# DC_Motor_Direction_Control.net
KiCad netlist of a schematic drawn in EAGLE
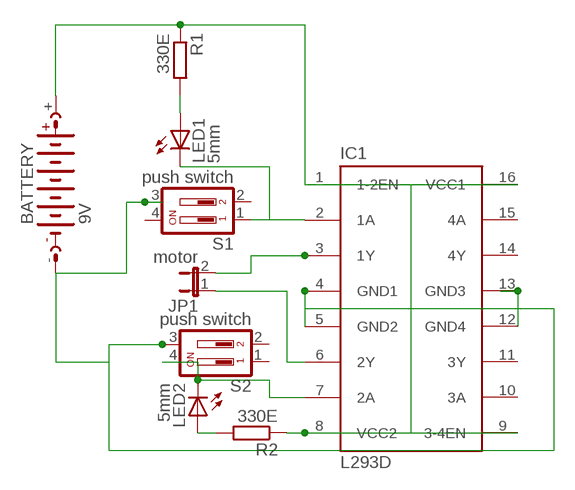
[diagram p0: schematic, sheet 1]

(export (version "E")
  (design (tool "Eeschema 10.0.6"))
  (components
    (comp (ref "BATTERY")
      (value "9V")
      (footprint "eagle-import:AB9V")
      (libsource (lib "eagle-import") (part "AB9V"))
    )
    (comp (ref "IC1")
      (value "L293D")
      (footprint "eagle-import:DIL16")
      (libsource (lib "eagle-import") (part "L293D"))
    )
    (comp (ref "JP1")
      (value "motor")
      (footprint "eagle-import:JP1")
      (libsource (lib "eagle-import") (part "JP1E"))
    )
    (comp (ref "LED1")
      (value "5mm")
      (footprint "eagle-import:LED5MM")
      (libsource (lib "eagle-import") (part "LED5MM"))
    )
    (comp (ref "LED2")
      (value "5mm")
      (footprint "eagle-import:LED5MM")
      (libsource (lib "eagle-import") (part "LED5MM"))
    )
    (comp (ref "R1")
      (value "330E")
      (footprint "eagle-import:0204_7")
      (libsource (lib "eagle-import") (part "R-EU_0204/7"))
    )
    (comp (ref "R2")
      (value "330E")
      (footprint "eagle-import:0204_7")
      (libsource (lib "eagle-import") (part "R-EU_0204/7"))
    )
    (comp (ref "S1")
      (value "push switch")
      (footprint "eagle-import:DS-02")
      (libsource (lib "eagle-import") (part "DS02"))
    )
    (comp (ref "S2")
      (value "push switch")
      (footprint "eagle-import:DS-02")
      (libsource (lib "eagle-import") (part "DS02"))
    )
  )
  (nets
    (net (code "1") (name "Net-(IC1-1-2EN)") (class "Default")
      (node (ref "BATTERY") (pin "+") (pinfunction "+_+") (pintype "passive"))
      (node (ref "IC1") (pin "1") (pinfunction "1-2EN_1") (pintype "input"))
      (node (ref "IC1") (pin "16") (pinfunction "VCC1_16") (pintype "power_in"))
      (node (ref "IC1") (pin "8") (pinfunction "VCC2_8") (pintype "power_in"))
      (node (ref "IC1") (pin "9") (pinfunction "3-4EN_9") (pintype "input"))
      (node (ref "R1") (pin "1") (pinfunction "1_1") (pintype "passive"))
      (node (ref "R2") (pin "1") (pinfunction "1_1") (pintype "passive"))
    )
    (net (code "2") (name "Net-(IC1-1A)") (class "Default")
      (node (ref "IC1") (pin "2") (pinfunction "1A_2") (pintype "input"))
      (node (ref "LED1") (pin "K") (pinfunction "C_K") (pintype "passive"))
      (node (ref "S1") (pin "1") (pinfunction "1_1") (pintype "passive"))
    )
    (net (code "3") (name "Net-(IC1-1Y)") (class "Default")
      (node (ref "IC1") (pin "3") (pinfunction "1Y_3") (pintype "output"))
      (node (ref "JP1") (pin "2") (pinfunction "2_2") (pintype "passive"))
    )
    (net (code "4") (name "Net-(IC1-2A)") (class "Default")
      (node (ref "IC1") (pin "7") (pinfunction "2A_7") (pintype "input"))
      (node (ref "LED2") (pin "K") (pinfunction "C_K") (pintype "passive"))
      (node (ref "S2") (pin "4") (pinfunction "4_4") (pintype "passive"))
    )
    (net (code "5") (name "Net-(IC1-2Y)") (class "Default")
      (node (ref "IC1") (pin "6") (pinfunction "2Y_6") (pintype "output"))
      (node (ref "JP1") (pin "1") (pinfunction "1_1") (pintype "passive"))
    )
    (net (code "6") (name "Net-(IC1-GND1)") (class "Default")
      (node (ref "BATTERY") (pin "-") (pinfunction "-_-") (pintype "passive"))
      (node (ref "IC1") (pin "12") (pinfunction "GND4_12") (pintype "power_in"))
      (node (ref "IC1") (pin "13") (pinfunction "GND3_13") (pintype "power_in"))
      (node (ref "IC1") (pin "4") (pinfunction "GND1_4") (pintype "power_in"))
      (node (ref "IC1") (pin "5") (pinfunction "GND2_5") (pintype "power_in"))
      (node (ref "S1") (pin "3") (pinfunction "3_3") (pintype "passive"))
      (node (ref "S2") (pin "3") (pinfunction "3_3") (pintype "passive"))
    )
    (net (code "7") (name "Net-(LED1-PadA)") (class "Default")
      (node (ref "LED1") (pin "A") (pinfunction "A_A") (pintype "passive"))
      (node (ref "R1") (pin "2") (pinfunction "2_2") (pintype "passive"))
    )
    (net (code "8") (name "Net-(LED2-PadA)") (class "Default")
      (node (ref "LED2") (pin "A") (pinfunction "A_A") (pintype "passive"))
      (node (ref "R2") (pin "2") (pinfunction "2_2") (pintype "passive"))
    )
    (net (code "9") (name "unconnected-(IC1-3A-Pad10)") (class "Default")
      (node (ref "IC1") (pin "10") (pinfunction "3A_10") (pintype "input"))
    )
    (net (code "10") (name "unconnected-(IC1-3Y-Pad11)") (class "Default")
      (node (ref "IC1") (pin "11") (pinfunction "3Y_11") (pintype "output"))
    )
    (net (code "11") (name "unconnected-(IC1-4A-Pad15)") (class "Default")
      (node (ref "IC1") (pin "15") (pinfunction "4A_15") (pintype "input"))
    )
    (net (code "12") (name "unconnected-(IC1-4Y-Pad14)") (class "Default")
      (node (ref "IC1") (pin "14") (pinfunction "4Y_14") (pintype "output"))
    )
    (net (code "13") (name "unconnected-(S1-Pad2)") (class "Default")
      (node (ref "S1") (pin "2") (pinfunction "2_2") (pintype "passive"))
    )
    (net (code "14") (name "unconnected-(S1-Pad4)") (class "Default")
      (node (ref "S1") (pin "4") (pinfunction "4_4") (pintype "passive"))
    )
    (net (code "15") (name "unconnected-(S2-Pad1)") (class "Default")
      (node (ref "S2") (pin "1") (pinfunction "1_1") (pintype "passive"))
    )
    (net (code "16") (name "unconnected-(S2-Pad2)") (class "Default")
      (node (ref "S2") (pin "2") (pinfunction "2_2") (pintype "passive"))
    )
  )
)
